# dev_kit.net
KiCad netlist of a schematic drawn in EasyEDA
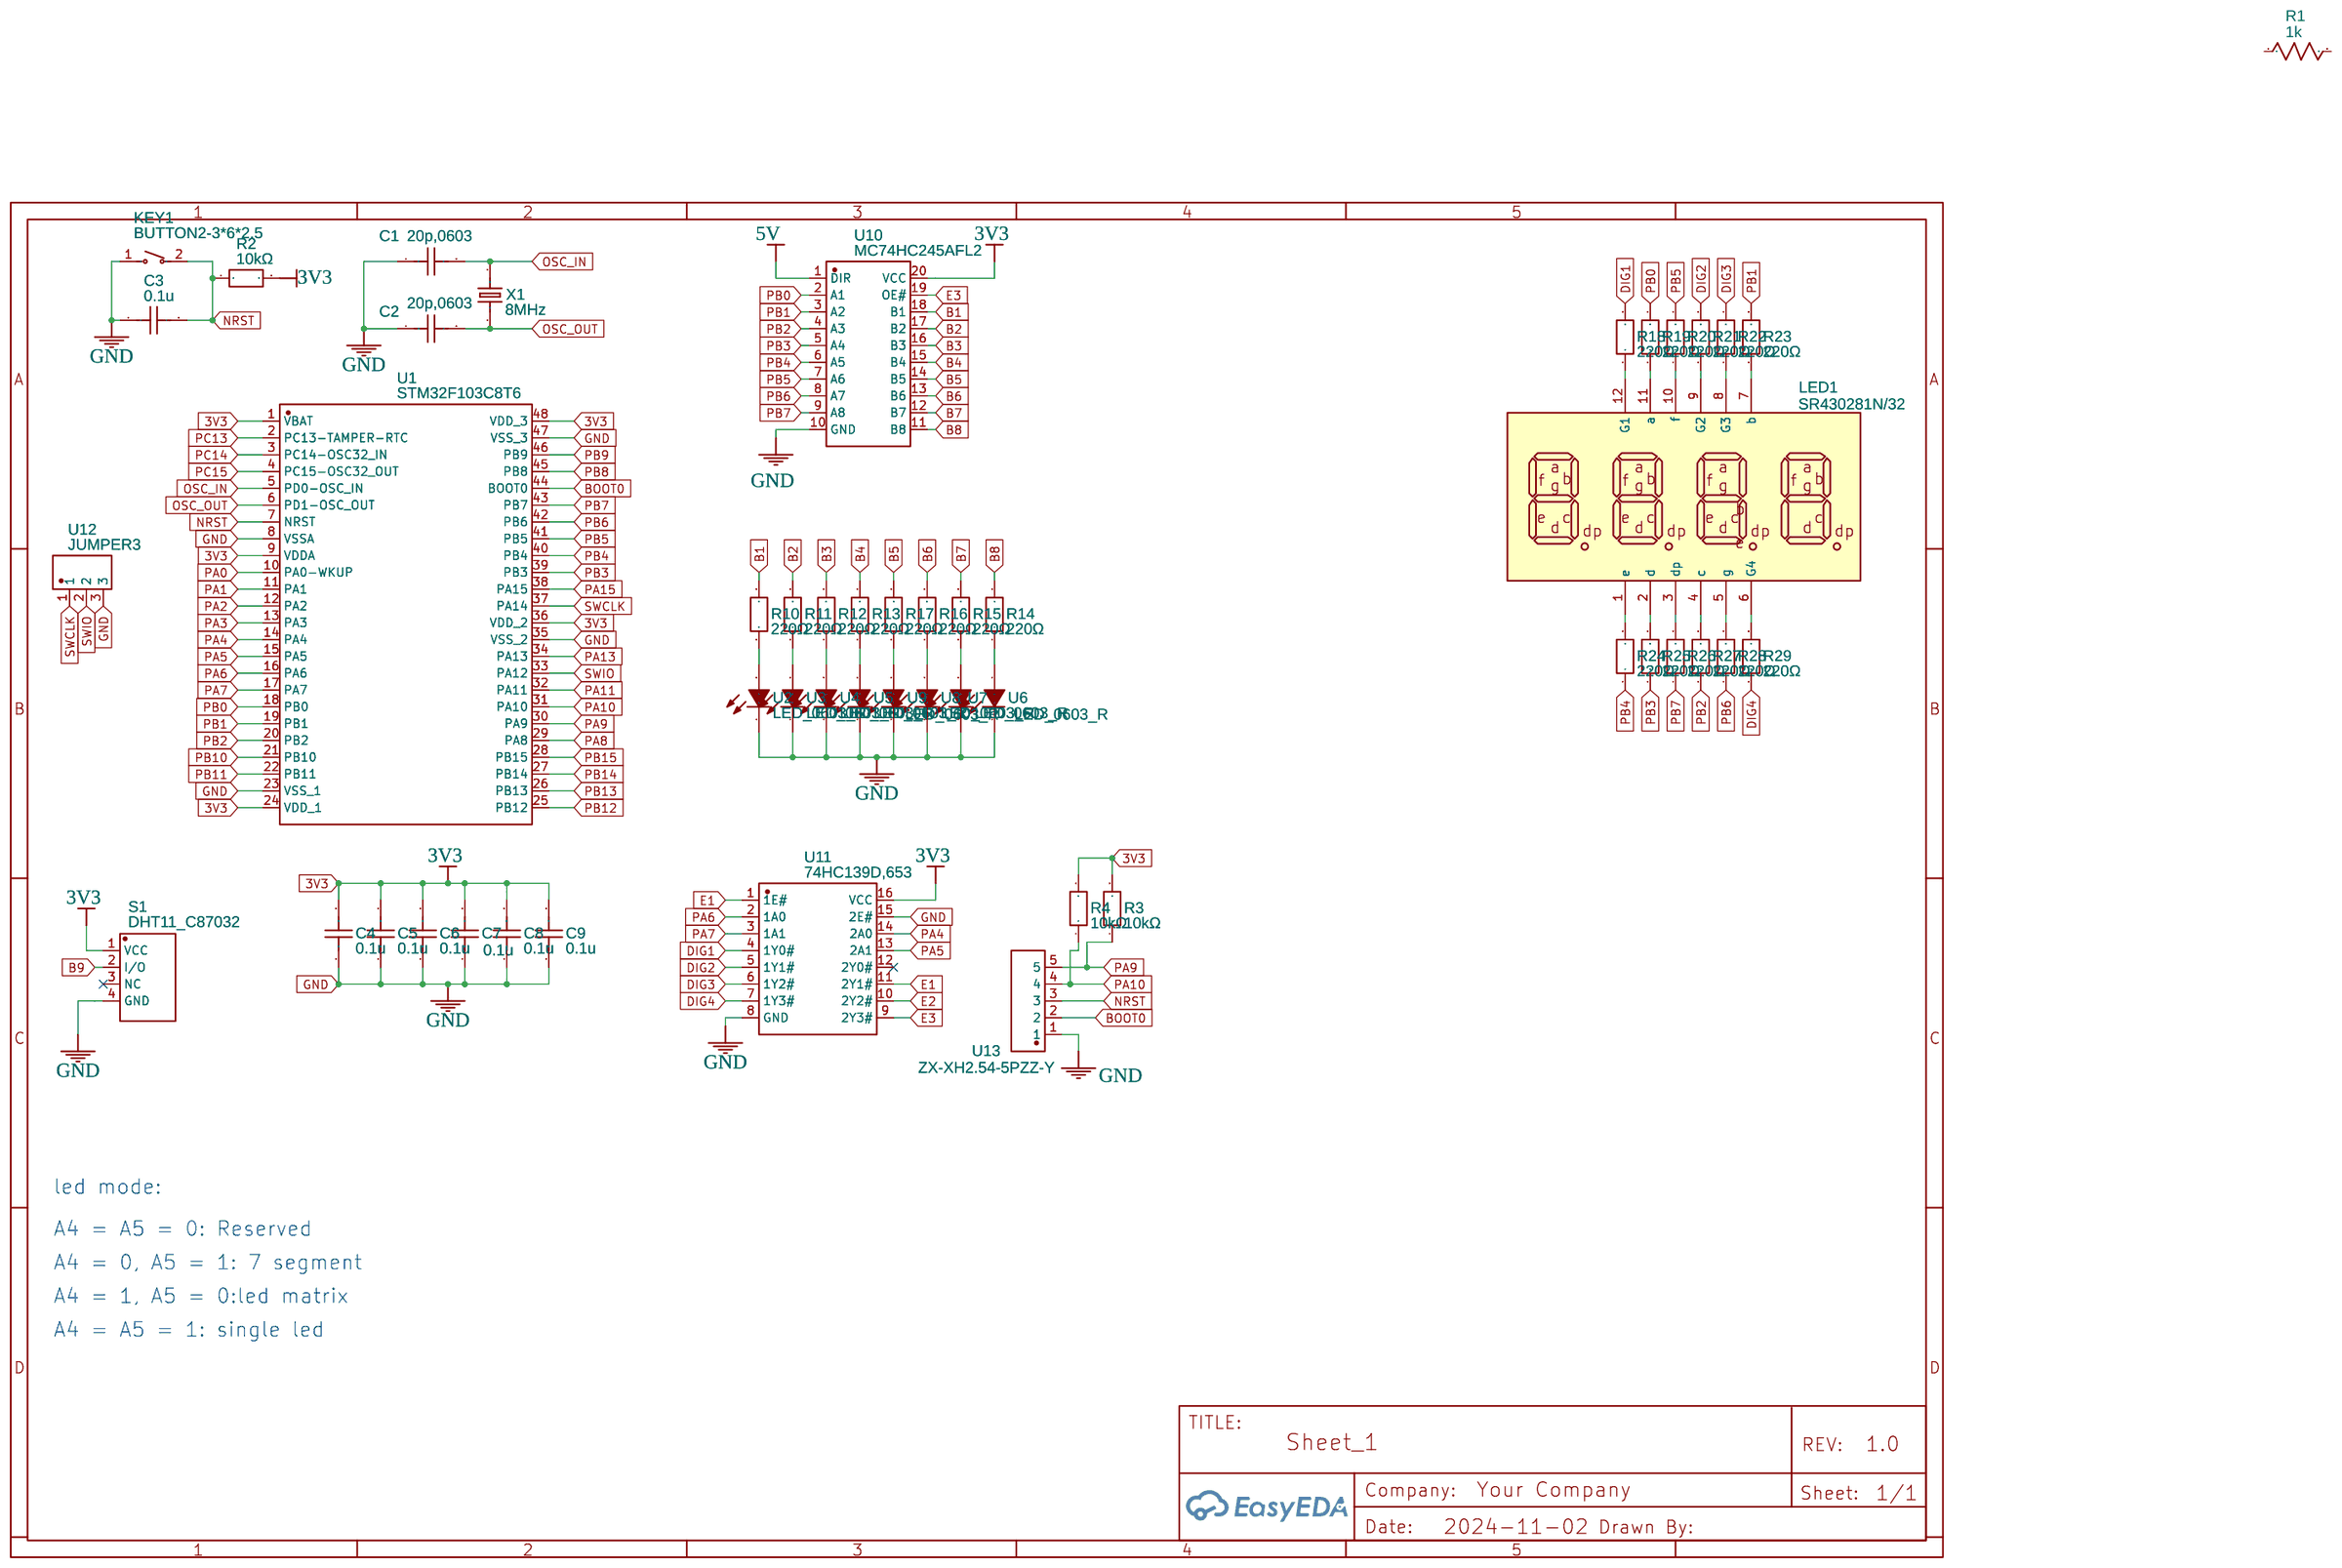
[diagram p0: schematic sheet]

(export (version "E")
  (design (tool "Eeschema 10.0.6"))
  (components
    (comp (ref "C1") (value "20p,0603") (libsource (lib "") (part "C_0603_US_1")))
    (comp (ref "C2") (value "20p,0603") (libsource (lib "") (part "C_0603_US_1")))
    (comp (ref "C3") (value "0.1u") (libsource (lib "") (part "C_0603_US_1")))
    (comp (ref "C4") (value "0.1u") (libsource (lib "") (part "C_0603_US")))
    (comp (ref "C5") (value "0.1u") (libsource (lib "") (part "C_0603_US")))
    (comp (ref "C6") (value "0.1u") (libsource (lib "") (part "C_0603_US")))
    (comp (ref "C7") (value "0.1u") (libsource (lib "") (part "C_0603_US")))
    (comp (ref "C8") (value "0.1u") (libsource (lib "") (part "C_0603_US")))
    (comp (ref "C9") (value "0.1u") (libsource (lib "") (part "C_0603_US")))
    (comp (ref "KEY1") (value "BUTTON2-3*6*2.5") (libsource (lib "") (part "BUTTON2-3*6*2.5")))
    (comp (ref "LED1")
      (value "SR430281N/32")
      (fields (field (name "Manufacturer") "ARKLED(方舟)"))
      (libsource (lib "") (part "SR430281N/32"))
    )
    (comp (ref "R1") (value "1k") (libsource (lib "") (part "R_0603_US")))
    (comp (ref "R2")
      (value "10kΩ")
      (fields (field (name "Manufacturer Part") "TD03E1002BT") (field (name "Manufacturer") "FH(风华)"))
      (libsource (lib "") (part "TD03E1002BT_1"))
    )
    (comp (ref "R3")
      (value "10kΩ")
      (fields (field (name "Manufacturer Part") "TD03E1002BT") (field (name "Manufacturer") "FH(风华)"))
      (libsource (lib "") (part "TD03E1002BT"))
    )
    (comp (ref "R4")
      (value "10kΩ")
      (fields (field (name "Manufacturer Part") "TD03E1002BT") (field (name "Manufacturer") "FH(风华)"))
      (libsource (lib "") (part "TD03E1002BT"))
    )
    (comp (ref "R10")
      (value "220Ω")
      (fields
        (field (name "Manufacturer Part") "CRCW0603220RFKEA")
        (field (name "Manufacturer") "VISHAY(威世)")
      )
      (libsource (lib "") (part "CRCW0603220RFKEA"))
    )
    (comp (ref "R11")
      (value "220Ω")
      (fields
        (field (name "Manufacturer Part") "CRCW0603220RFKEA")
        (field (name "Manufacturer") "VISHAY(威世)")
      )
      (libsource (lib "") (part "CRCW0603220RFKEA"))
    )
    (comp (ref "R12")
      (value "220Ω")
      (fields
        (field (name "Manufacturer Part") "CRCW0603220RFKEA")
        (field (name "Manufacturer") "VISHAY(威世)")
      )
      (libsource (lib "") (part "CRCW0603220RFKEA"))
    )
    (comp (ref "R13")
      (value "220Ω")
      (fields
        (field (name "Manufacturer Part") "CRCW0603220RFKEA")
        (field (name "Manufacturer") "VISHAY(威世)")
      )
      (libsource (lib "") (part "CRCW0603220RFKEA"))
    )
    (comp (ref "R14")
      (value "220Ω")
      (fields
        (field (name "Manufacturer Part") "CRCW0603220RFKEA")
        (field (name "Manufacturer") "VISHAY(威世)")
      )
      (libsource (lib "") (part "CRCW0603220RFKEA"))
    )
    (comp (ref "R15")
      (value "220Ω")
      (fields
        (field (name "Manufacturer Part") "CRCW0603220RFKEA")
        (field (name "Manufacturer") "VISHAY(威世)")
      )
      (libsource (lib "") (part "CRCW0603220RFKEA"))
    )
    (comp (ref "R16")
      (value "220Ω")
      (fields
        (field (name "Manufacturer Part") "CRCW0603220RFKEA")
        (field (name "Manufacturer") "VISHAY(威世)")
      )
      (libsource (lib "") (part "CRCW0603220RFKEA"))
    )
    (comp (ref "R17")
      (value "220Ω")
      (fields
        (field (name "Manufacturer Part") "CRCW0603220RFKEA")
        (field (name "Manufacturer") "VISHAY(威世)")
      )
      (libsource (lib "") (part "CRCW0603220RFKEA"))
    )
    (comp (ref "R18")
      (value "220Ω")
      (fields
        (field (name "Manufacturer Part") "CRCW0603220RFKEA")
        (field (name "Manufacturer") "VISHAY(威世)")
      )
      (libsource (lib "") (part "CRCW0603220RFKEA"))
    )
    (comp (ref "R19")
      (value "220Ω")
      (fields
        (field (name "Manufacturer Part") "CRCW0603220RFKEA")
        (field (name "Manufacturer") "VISHAY(威世)")
      )
      (libsource (lib "") (part "CRCW0603220RFKEA"))
    )
    (comp (ref "R20")
      (value "220Ω")
      (fields
        (field (name "Manufacturer Part") "CRCW0603220RFKEA")
        (field (name "Manufacturer") "VISHAY(威世)")
      )
      (libsource (lib "") (part "CRCW0603220RFKEA"))
    )
    (comp (ref "R21")
      (value "220Ω")
      (fields
        (field (name "Manufacturer Part") "CRCW0603220RFKEA")
        (field (name "Manufacturer") "VISHAY(威世)")
      )
      (libsource (lib "") (part "CRCW0603220RFKEA"))
    )
    (comp (ref "R22")
      (value "220Ω")
      (fields
        (field (name "Manufacturer Part") "CRCW0603220RFKEA")
        (field (name "Manufacturer") "VISHAY(威世)")
      )
      (libsource (lib "") (part "CRCW0603220RFKEA"))
    )
    (comp (ref "R23")
      (value "220Ω")
      (fields
        (field (name "Manufacturer Part") "CRCW0603220RFKEA")
        (field (name "Manufacturer") "VISHAY(威世)")
      )
      (libsource (lib "") (part "CRCW0603220RFKEA"))
    )
    (comp (ref "R24")
      (value "220Ω")
      (fields
        (field (name "Manufacturer Part") "CRCW0603220RFKEA")
        (field (name "Manufacturer") "VISHAY(威世)")
      )
      (libsource (lib "") (part "CRCW0603220RFKEA"))
    )
    (comp (ref "R25")
      (value "220Ω")
      (fields
        (field (name "Manufacturer Part") "CRCW0603220RFKEA")
        (field (name "Manufacturer") "VISHAY(威世)")
      )
      (libsource (lib "") (part "CRCW0603220RFKEA"))
    )
    (comp (ref "R26")
      (value "220Ω")
      (fields
        (field (name "Manufacturer Part") "CRCW0603220RFKEA")
        (field (name "Manufacturer") "VISHAY(威世)")
      )
      (libsource (lib "") (part "CRCW0603220RFKEA"))
    )
    (comp (ref "R27")
      (value "220Ω")
      (fields
        (field (name "Manufacturer Part") "CRCW0603220RFKEA")
        (field (name "Manufacturer") "VISHAY(威世)")
      )
      (libsource (lib "") (part "CRCW0603220RFKEA"))
    )
    (comp (ref "R28")
      (value "220Ω")
      (fields
        (field (name "Manufacturer Part") "CRCW0603220RFKEA")
        (field (name "Manufacturer") "VISHAY(威世)")
      )
      (libsource (lib "") (part "CRCW0603220RFKEA"))
    )
    (comp (ref "R29")
      (value "220Ω")
      (fields
        (field (name "Manufacturer Part") "CRCW0603220RFKEA")
        (field (name "Manufacturer") "VISHAY(威世)")
      )
      (libsource (lib "") (part "CRCW0603220RFKEA"))
    )
    (comp (ref "S1")
      (value "DHT11_C87032")
      (fields (field (name "Manufacturer Part") "DHT11") (field (name "Manufacturer") "AOSONG"))
      (libsource (lib "") (part "DHT11_C87032"))
    )
    (comp (ref "U1")
      (value "STM32F103C8T6")
      (fields (field (name "Manufacturer") "ST(意法半导体)"))
      (libsource (lib "") (part "STM32F103C8T6"))
    )
    (comp (ref "U2") (value "LED_0603_R") (libsource (lib "") (part "LED_0603_R")))
    (comp (ref "U3") (value "LED_0603_R") (libsource (lib "") (part "LED_0603_R")))
    (comp (ref "U4") (value "LED_0603_R") (libsource (lib "") (part "LED_0603_R")))
    (comp (ref "U5") (value "LED_0603_R") (libsource (lib "") (part "LED_0603_R")))
    (comp (ref "U6") (value "LED_0603_R") (libsource (lib "") (part "LED_0603_R")))
    (comp (ref "U7") (value "LED_0603_R") (libsource (lib "") (part "LED_0603_R")))
    (comp (ref "U8") (value "LED_0603_R") (libsource (lib "") (part "LED_0603_R")))
    (comp (ref "U9") (value "LED_0603_R") (libsource (lib "") (part "LED_0603_R")))
    (comp (ref "U10")
      (value "MC74HC245AFL2")
      (fields (field (name "Manufacturer") "MOTOROLA(摩托罗拉)"))
      (libsource (lib "") (part "MC74HC245AFL2"))
    )
    (comp (ref "U11")
      (value "74HC139D,653")
      (fields (field (name "Manufacturer") "Nexperia(安世)"))
      (libsource (lib "") (part "74HC139D,653"))
    )
    (comp (ref "U12")
      (value "JUMPER3")
      (fields (field (name "Manufacturer Part") "Jumper3"))
      (libsource (lib "") (part "JUMPER3"))
    )
    (comp (ref "U13")
      (value "ZX-XH2.54-5PZZ-Y")
      (fields (field (name "Manufacturer") "Megastar(兆星)"))
      (libsource (lib "") (part "ZX-XH2.54-5PZZ-Y"))
    )
    (comp (ref "X1")
      (value "8MHz")
      (fields
        (field (name "Manufacturer Part") "49S-8.00-20-10-10/A")
        (field (name "Manufacturer") "LIMING(利明)")
      )
      (libsource (lib "") (part "49S-8.00-20-10-10/A"))
    )
  )
  (nets
    (net (code "1") (name "3V3") (class "Default")
      (node (ref "C4") (pin "2") (pinfunction "2_2") (pintype "unspecified"))
      (node (ref "C5") (pin "2") (pinfunction "2_2") (pintype "unspecified"))
      (node (ref "C6") (pin "2") (pinfunction "2_2") (pintype "unspecified"))
      (node (ref "C7") (pin "2") (pinfunction "2_2") (pintype "unspecified"))
      (node (ref "C8") (pin "2") (pinfunction "2_2") (pintype "unspecified"))
      (node (ref "C9") (pin "2") (pinfunction "2_2") (pintype "unspecified"))
      (node (ref "R2") (pin "2") (pinfunction "2_2") (pintype "unspecified"))
      (node (ref "R3") (pin "2") (pinfunction "2_2") (pintype "unspecified"))
      (node (ref "R4") (pin "2") (pinfunction "2_2") (pintype "unspecified"))
      (node (ref "S1") (pin "1") (pinfunction "VCC_1") (pintype "unspecified"))
      (node (ref "U1") (pin "1") (pinfunction "VBAT_1") (pintype "unspecified"))
      (node (ref "U1") (pin "24") (pinfunction "VDD_1_24") (pintype "unspecified"))
      (node (ref "U1") (pin "36") (pinfunction "VDD_2_36") (pintype "unspecified"))
      (node (ref "U1") (pin "48") (pinfunction "VDD_3_48") (pintype "unspecified"))
      (node (ref "U1") (pin "9") (pinfunction "VDDA_9") (pintype "unspecified"))
      (node (ref "U10") (pin "20") (pinfunction "VCC_20") (pintype "unspecified"))
      (node (ref "U11") (pin "16") (pinfunction "VCC_16") (pintype "unspecified"))
    )
    (net (code "2") (name "5V") (class "Default")
      (node (ref "U10") (pin "1") (pinfunction "DIR_1") (pintype "unspecified"))
    )
    (net (code "3") (name "B1") (class "Default")
      (node (ref "R10") (pin "2") (pinfunction "2_2") (pintype "unspecified"))
      (node (ref "U10") (pin "18") (pinfunction "B1_18") (pintype "unspecified"))
    )
    (net (code "4") (name "B2") (class "Default")
      (node (ref "R11") (pin "2") (pinfunction "2_2") (pintype "unspecified"))
      (node (ref "U10") (pin "17") (pinfunction "B2_17") (pintype "unspecified"))
    )
    (net (code "5") (name "B3") (class "Default")
      (node (ref "R12") (pin "2") (pinfunction "2_2") (pintype "unspecified"))
      (node (ref "U10") (pin "16") (pinfunction "B3_16") (pintype "unspecified"))
    )
    (net (code "6") (name "B4") (class "Default")
      (node (ref "R13") (pin "2") (pinfunction "2_2") (pintype "unspecified"))
      (node (ref "U10") (pin "15") (pinfunction "B4_15") (pintype "unspecified"))
    )
    (net (code "7") (name "B5") (class "Default")
      (node (ref "R17") (pin "2") (pinfunction "2_2") (pintype "unspecified"))
      (node (ref "U10") (pin "14") (pinfunction "B5_14") (pintype "unspecified"))
    )
    (net (code "8") (name "B6") (class "Default")
      (node (ref "R16") (pin "2") (pinfunction "2_2") (pintype "unspecified"))
      (node (ref "U10") (pin "13") (pinfunction "B6_13") (pintype "unspecified"))
    )
    (net (code "9") (name "B7") (class "Default")
      (node (ref "R15") (pin "2") (pinfunction "2_2") (pintype "unspecified"))
      (node (ref "U10") (pin "12") (pinfunction "B7_12") (pintype "unspecified"))
    )
    (net (code "10") (name "B8") (class "Default")
      (node (ref "R14") (pin "2") (pinfunction "2_2") (pintype "unspecified"))
      (node (ref "U10") (pin "11") (pinfunction "B8_11") (pintype "unspecified"))
    )
    (net (code "11") (name "B9") (class "Default")
      (node (ref "S1") (pin "2") (pinfunction "I/O_2") (pintype "unspecified"))
    )
    (net (code "12") (name "BOOT0") (class "Default")
      (node (ref "U1") (pin "44") (pinfunction "BOOT0_44") (pintype "unspecified"))
      (node (ref "U13") (pin "2") (pinfunction "2_2") (pintype "unspecified"))
    )
    (net (code "13") (name "DIG1") (class "Default")
      (node (ref "R18") (pin "2") (pinfunction "2_2") (pintype "unspecified"))
      (node (ref "U11") (pin "4") (pinfunction "1Y0#_4") (pintype "unspecified"))
    )
    (net (code "14") (name "DIG2") (class "Default")
      (node (ref "R21") (pin "2") (pinfunction "2_2") (pintype "unspecified"))
      (node (ref "U11") (pin "5") (pinfunction "1Y1#_5") (pintype "unspecified"))
    )
    (net (code "15") (name "DIG3") (class "Default")
      (node (ref "R22") (pin "2") (pinfunction "2_2") (pintype "unspecified"))
      (node (ref "U11") (pin "6") (pinfunction "1Y2#_6") (pintype "unspecified"))
    )
    (net (code "16") (name "DIG4") (class "Default")
      (node (ref "R29") (pin "1") (pinfunction "1_1") (pintype "unspecified"))
      (node (ref "U11") (pin "7") (pinfunction "1Y3#_7") (pintype "unspecified"))
    )
    (net (code "17") (name "E1") (class "Default")
      (node (ref "U11") (pin "1") (pinfunction "1E#_1") (pintype "unspecified"))
      (node (ref "U11") (pin "11") (pinfunction "2Y1#_11") (pintype "unspecified"))
    )
    (net (code "18") (name "E2") (class "Default")
      (node (ref "U11") (pin "10") (pinfunction "2Y2#_10") (pintype "unspecified"))
    )
    (net (code "19") (name "E3") (class "Default")
      (node (ref "U10") (pin "19") (pinfunction "OE#_19") (pintype "unspecified"))
      (node (ref "U11") (pin "9") (pinfunction "2Y3#_9") (pintype "unspecified"))
    )
    (net (code "20") (name "GND") (class "Default")
      (node (ref "C1") (pin "1") (pinfunction "1_1") (pintype "unspecified"))
      (node (ref "C2") (pin "1") (pinfunction "1_1") (pintype "unspecified"))
      (node (ref "C3") (pin "1") (pinfunction "1_1") (pintype "unspecified"))
      (node (ref "C4") (pin "1") (pinfunction "1_1") (pintype "unspecified"))
      (node (ref "C5") (pin "1") (pinfunction "1_1") (pintype "unspecified"))
      (node (ref "C6") (pin "1") (pinfunction "1_1") (pintype "unspecified"))
      (node (ref "C7") (pin "1") (pinfunction "1_1") (pintype "unspecified"))
      (node (ref "C8") (pin "1") (pinfunction "1_1") (pintype "unspecified"))
      (node (ref "C9") (pin "1") (pinfunction "1_1") (pintype "unspecified"))
      (node (ref "KEY1") (pin "1") (pinfunction "1_1") (pintype "unspecified"))
      (node (ref "S1") (pin "4") (pinfunction "GND_4") (pintype "unspecified"))
      (node (ref "U1") (pin "23") (pinfunction "VSS_1_23") (pintype "unspecified"))
      (node (ref "U1") (pin "35") (pinfunction "VSS_2_35") (pintype "unspecified"))
      (node (ref "U1") (pin "47") (pinfunction "VSS_3_47") (pintype "unspecified"))
      (node (ref "U1") (pin "8") (pinfunction "VSSA_8") (pintype "unspecified"))
      (node (ref "U10") (pin "10") (pinfunction "GND_10") (pintype "unspecified"))
      (node (ref "U11") (pin "15") (pinfunction "2E#_15") (pintype "unspecified"))
      (node (ref "U11") (pin "8") (pinfunction "GND_8") (pintype "unspecified"))
      (node (ref "U12") (pin "3") (pinfunction "3_3") (pintype "unspecified"))
      (node (ref "U13") (pin "1") (pinfunction "1_1") (pintype "unspecified"))
      (node (ref "U2") (pin "1") (pinfunction "-_1") (pintype "input"))
      (node (ref "U3") (pin "1") (pinfunction "-_1") (pintype "input"))
      (node (ref "U4") (pin "1") (pinfunction "-_1") (pintype "input"))
      (node (ref "U5") (pin "1") (pinfunction "-_1") (pintype "input"))
      (node (ref "U6") (pin "1") (pinfunction "-_1") (pintype "input"))
      (node (ref "U7") (pin "1") (pinfunction "-_1") (pintype "input"))
      (node (ref "U8") (pin "1") (pinfunction "-_1") (pintype "input"))
      (node (ref "U9") (pin "1") (pinfunction "-_1") (pintype "input"))
    )
    (net (code "21") (name "NRST") (class "Default")
      (node (ref "C3") (pin "2") (pinfunction "2_2") (pintype "unspecified"))
      (node (ref "KEY1") (pin "2") (pinfunction "2_2") (pintype "unspecified"))
      (node (ref "R2") (pin "1") (pinfunction "1_1") (pintype "unspecified"))
      (node (ref "U1") (pin "7") (pinfunction "NRST_7") (pintype "unspecified"))
      (node (ref "U13") (pin "3") (pinfunction "3_3") (pintype "unspecified"))
    )
    (net (code "22") (name "Net-(LED1-G1)") (class "Default")
      (node (ref "LED1") (pin "12") (pinfunction "G1_12") (pintype "input"))
      (node (ref "R18") (pin "1") (pinfunction "1_1") (pintype "unspecified"))
    )
    (net (code "23") (name "Net-(LED1-G2)") (class "Default")
      (node (ref "LED1") (pin "9") (pinfunction "G2_9") (pintype "input"))
      (node (ref "R21") (pin "1") (pinfunction "1_1") (pintype "unspecified"))
    )
    (net (code "24") (name "Net-(LED1-G3)") (class "Default")
      (node (ref "LED1") (pin "8") (pinfunction "G3_8") (pintype "input"))
      (node (ref "R22") (pin "1") (pinfunction "1_1") (pintype "unspecified"))
    )
    (net (code "25") (name "Net-(LED1-G4)") (class "Default")
      (node (ref "LED1") (pin "6") (pinfunction "G4_6") (pintype "input"))
      (node (ref "R29") (pin "2") (pinfunction "2_2") (pintype "unspecified"))
    )
    (net (code "26") (name "Net-(LED1-a)") (class "Default")
      (node (ref "LED1") (pin "11") (pinfunction "a_11") (pintype "input"))
      (node (ref "R19") (pin "1") (pinfunction "1_1") (pintype "unspecified"))
    )
    (net (code "27") (name "Net-(LED1-b)") (class "Default")
      (node (ref "LED1") (pin "7") (pinfunction "b_7") (pintype "input"))
      (node (ref "R23") (pin "1") (pinfunction "1_1") (pintype "unspecified"))
    )
    (net (code "28") (name "Net-(LED1-c)") (class "Default")
      (node (ref "LED1") (pin "4") (pinfunction "c_4") (pintype "input"))
      (node (ref "R27") (pin "2") (pinfunction "2_2") (pintype "unspecified"))
    )
    (net (code "29") (name "Net-(LED1-d)") (class "Default")
      (node (ref "LED1") (pin "2") (pinfunction "d_2") (pintype "input"))
      (node (ref "R25") (pin "2") (pinfunction "2_2") (pintype "unspecified"))
    )
    (net (code "30") (name "Net-(LED1-dp)") (class "Default")
      (node (ref "LED1") (pin "3") (pinfunction "dp_3") (pintype "input"))
      (node (ref "R26") (pin "2") (pinfunction "2_2") (pintype "unspecified"))
    )
    (net (code "31") (name "Net-(LED1-e)") (class "Default")
      (node (ref "LED1") (pin "1") (pinfunction "e_1") (pintype "input"))
      (node (ref "R24") (pin "2") (pinfunction "2_2") (pintype "unspecified"))
    )
    (net (code "32") (name "Net-(LED1-f)") (class "Default")
      (node (ref "LED1") (pin "10") (pinfunction "f_10") (pintype "input"))
      (node (ref "R20") (pin "1") (pinfunction "1_1") (pintype "unspecified"))
    )
    (net (code "33") (name "Net-(LED1-g)") (class "Default")
      (node (ref "LED1") (pin "5") (pinfunction "g_5") (pintype "input"))
      (node (ref "R28") (pin "2") (pinfunction "2_2") (pintype "unspecified"))
    )
    (net (code "34") (name "Net-(U2-+)") (class "Default")
      (node (ref "R10") (pin "1") (pinfunction "1_1") (pintype "unspecified"))
      (node (ref "U2") (pin "2") (pinfunction "+_2") (pintype "input"))
    )
    (net (code "35") (name "Net-(U3-+)") (class "Default")
      (node (ref "R11") (pin "1") (pinfunction "1_1") (pintype "unspecified"))
      (node (ref "U3") (pin "2") (pinfunction "+_2") (pintype "input"))
    )
    (net (code "36") (name "Net-(U4-+)") (class "Default")
      (node (ref "R12") (pin "1") (pinfunction "1_1") (pintype "unspecified"))
      (node (ref "U4") (pin "2") (pinfunction "+_2") (pintype "input"))
    )
    (net (code "37") (name "Net-(U5-+)") (class "Default")
      (node (ref "R13") (pin "1") (pinfunction "1_1") (pintype "unspecified"))
      (node (ref "U5") (pin "2") (pinfunction "+_2") (pintype "input"))
    )
    (net (code "38") (name "Net-(U6-+)") (class "Default")
      (node (ref "R14") (pin "1") (pinfunction "1_1") (pintype "unspecified"))
      (node (ref "U6") (pin "2") (pinfunction "+_2") (pintype "input"))
    )
    (net (code "39") (name "Net-(U7-+)") (class "Default")
      (node (ref "R15") (pin "1") (pinfunction "1_1") (pintype "unspecified"))
      (node (ref "U7") (pin "2") (pinfunction "+_2") (pintype "input"))
    )
    (net (code "40") (name "Net-(U8-+)") (class "Default")
      (node (ref "R16") (pin "1") (pinfunction "1_1") (pintype "unspecified"))
      (node (ref "U8") (pin "2") (pinfunction "+_2") (pintype "input"))
    )
    (net (code "41") (name "Net-(U9-+)") (class "Default")
      (node (ref "R17") (pin "1") (pinfunction "1_1") (pintype "unspecified"))
      (node (ref "U9") (pin "2") (pinfunction "+_2") (pintype "input"))
    )
    (net (code "42") (name "OSC_IN") (class "Default")
      (node (ref "C1") (pin "2") (pinfunction "2_2") (pintype "unspecified"))
      (node (ref "U1") (pin "5") (pinfunction "PD0-OSC_IN_5") (pintype "unspecified"))
      (node (ref "X1") (pin "2") (pinfunction "2_2") (pintype "unspecified"))
    )
    (net (code "43") (name "OSC_OUT") (class "Default")
      (node (ref "C2") (pin "2") (pinfunction "2_2") (pintype "unspecified"))
      (node (ref "U1") (pin "6") (pinfunction "PD1-OSC_OUT_6") (pintype "unspecified"))
      (node (ref "X1") (pin "1") (pinfunction "1_1") (pintype "unspecified"))
    )
    (net (code "44") (name "PA0") (class "Default")
      (node (ref "U1") (pin "10") (pinfunction "PA0-WKUP_10") (pintype "unspecified"))
    )
    (net (code "45") (name "PA1") (class "Default")
      (node (ref "U1") (pin "11") (pinfunction "PA1_11") (pintype "unspecified"))
    )
    (net (code "46") (name "PA2") (class "Default")
      (node (ref "U1") (pin "12") (pinfunction "PA2_12") (pintype "unspecified"))
    )
    (net (code "47") (name "PA3") (class "Default")
      (node (ref "U1") (pin "13") (pinfunction "PA3_13") (pintype "unspecified"))
    )
    (net (code "48") (name "PA4") (class "Default")
      (node (ref "U1") (pin "14") (pinfunction "PA4_14") (pintype "unspecified"))
      (node (ref "U11") (pin "14") (pinfunction "2A0_14") (pintype "unspecified"))
    )
    (net (code "49") (name "PA5") (class "Default")
      (node (ref "U1") (pin "15") (pinfunction "PA5_15") (pintype "unspecified"))
      (node (ref "U11") (pin "13") (pinfunction "2A1_13") (pintype "unspecified"))
    )
    (net (code "50") (name "PA6") (class "Default")
      (node (ref "U1") (pin "16") (pinfunction "PA6_16") (pintype "unspecified"))
      (node (ref "U11") (pin "2") (pinfunction "1A0_2") (pintype "unspecified"))
    )
    (net (code "51") (name "PA7") (class "Default")
      (node (ref "U1") (pin "17") (pinfunction "PA7_17") (pintype "unspecified"))
      (node (ref "U11") (pin "3") (pinfunction "1A1_3") (pintype "unspecified"))
    )
    (net (code "52") (name "PA8") (class "Default")
      (node (ref "U1") (pin "29") (pinfunction "PA8_29") (pintype "unspecified"))
    )
    (net (code "53") (name "PA9") (class "Default")
      (node (ref "R3") (pin "1") (pinfunction "1_1") (pintype "unspecified"))
      (node (ref "U1") (pin "30") (pinfunction "PA9_30") (pintype "unspecified"))
      (node (ref "U13") (pin "5") (pinfunction "5_5") (pintype "unspecified"))
    )
    (net (code "54") (name "PA10") (class "Default")
      (node (ref "R4") (pin "1") (pinfunction "1_1") (pintype "unspecified"))
      (node (ref "U1") (pin "31") (pinfunction "PA10_31") (pintype "unspecified"))
      (node (ref "U13") (pin "4") (pinfunction "4_4") (pintype "unspecified"))
    )
    (net (code "55") (name "PA11") (class "Default")
      (node (ref "U1") (pin "32") (pinfunction "PA11_32") (pintype "unspecified"))
    )
    (net (code "56") (name "PA13") (class "Default")
      (node (ref "U1") (pin "34") (pinfunction "PA13_34") (pintype "unspecified"))
    )
    (net (code "57") (name "PA15") (class "Default")
      (node (ref "U1") (pin "38") (pinfunction "PA15_38") (pintype "unspecified"))
    )
    (net (code "58") (name "PB0") (class "Default")
      (node (ref "R19") (pin "2") (pinfunction "2_2") (pintype "unspecified"))
      (node (ref "U1") (pin "18") (pinfunction "PB0_18") (pintype "unspecified"))
      (node (ref "U10") (pin "2") (pinfunction "A1_2") (pintype "unspecified"))
    )
    (net (code "59") (name "PB1") (class "Default")
      (node (ref "R23") (pin "2") (pinfunction "2_2") (pintype "unspecified"))
      (node (ref "U1") (pin "19") (pinfunction "PB1_19") (pintype "unspecified"))
      (node (ref "U10") (pin "3") (pinfunction "A2_3") (pintype "unspecified"))
    )
    (net (code "60") (name "PB2") (class "Default")
      (node (ref "R27") (pin "1") (pinfunction "1_1") (pintype "unspecified"))
      (node (ref "U1") (pin "20") (pinfunction "PB2_20") (pintype "unspecified"))
      (node (ref "U10") (pin "4") (pinfunction "A3_4") (pintype "unspecified"))
    )
    (net (code "61") (name "PB3") (class "Default")
      (node (ref "R25") (pin "1") (pinfunction "1_1") (pintype "unspecified"))
      (node (ref "U1") (pin "39") (pinfunction "PB3_39") (pintype "unspecified"))
      (node (ref "U10") (pin "5") (pinfunction "A4_5") (pintype "unspecified"))
    )
    (net (code "62") (name "PB4") (class "Default")
      (node (ref "R24") (pin "1") (pinfunction "1_1") (pintype "unspecified"))
      (node (ref "U1") (pin "40") (pinfunction "PB4_40") (pintype "unspecified"))
      (node (ref "U10") (pin "6") (pinfunction "A5_6") (pintype "unspecified"))
    )
    (net (code "63") (name "PB5") (class "Default")
      (node (ref "R20") (pin "2") (pinfunction "2_2") (pintype "unspecified"))
      (node (ref "U1") (pin "41") (pinfunction "PB5_41") (pintype "unspecified"))
      (node (ref "U10") (pin "7") (pinfunction "A6_7") (pintype "unspecified"))
    )
    (net (code "64") (name "PB6") (class "Default")
      (node (ref "R28") (pin "1") (pinfunction "1_1") (pintype "unspecified"))
      (node (ref "U1") (pin "42") (pinfunction "PB6_42") (pintype "unspecified"))
      (node (ref "U10") (pin "8") (pinfunction "A7_8") (pintype "unspecified"))
    )
    (net (code "65") (name "PB7") (class "Default")
      (node (ref "R26") (pin "1") (pinfunction "1_1") (pintype "unspecified"))
      (node (ref "U1") (pin "43") (pinfunction "PB7_43") (pintype "unspecified"))
      (node (ref "U10") (pin "9") (pinfunction "A8_9") (pintype "unspecified"))
    )
    (net (code "66") (name "PB8") (class "Default")
      (node (ref "U1") (pin "45") (pinfunction "PB8_45") (pintype "unspecified"))
    )
    (net (code "67") (name "PB9") (class "Default")
      (node (ref "U1") (pin "46") (pinfunction "PB9_46") (pintype "unspecified"))
    )
    (net (code "68") (name "PB10") (class "Default")
      (node (ref "U1") (pin "21") (pinfunction "PB10_21") (pintype "unspecified"))
    )
    (net (code "69") (name "PB11") (class "Default")
      (node (ref "U1") (pin "22") (pinfunction "PB11_22") (pintype "unspecified"))
    )
    (net (code "70") (name "PB12") (class "Default")
      (node (ref "U1") (pin "25") (pinfunction "PB12_25") (pintype "unspecified"))
    )
    (net (code "71") (name "PB13") (class "Default")
      (node (ref "U1") (pin "26") (pinfunction "PB13_26") (pintype "unspecified"))
    )
    (net (code "72") (name "PB14") (class "Default")
      (node (ref "U1") (pin "27") (pinfunction "PB14_27") (pintype "unspecified"))
    )
    (net (code "73") (name "PB15") (class "Default")
      (node (ref "U1") (pin "28") (pinfunction "PB15_28") (pintype "unspecified"))
    )
    (net (code "74") (name "PC13") (class "Default")
      (node (ref "U1") (pin "2") (pinfunction "PC13-TAMPER-RTC_2") (pintype "unspecified"))
    )
    (net (code "75") (name "PC14") (class "Default")
      (node (ref "U1") (pin "3") (pinfunction "PC14-OSC32_IN_3") (pintype "unspecified"))
    )
    (net (code "76") (name "PC15") (class "Default")
      (node (ref "U1") (pin "4") (pinfunction "PC15-OSC32_OUT_4") (pintype "unspecified"))
    )
    (net (code "77") (name "SWCLK") (class "Default")
      (node (ref "U1") (pin "37") (pinfunction "PA14_37") (pintype "unspecified"))
      (node (ref "U12") (pin "1") (pinfunction "1_1") (pintype "unspecified"))
    )
    (net (code "78") (name "SWIO") (class "Default")
      (node (ref "U1") (pin "33") (pinfunction "PA12_33") (pintype "unspecified"))
      (node (ref "U12") (pin "2") (pinfunction "2_2") (pintype "unspecified"))
    )
    (net (code "79") (name "unconnected-(R1-Pad1)") (class "Default")
      (node (ref "R1") (pin "1") (pinfunction "1_1") (pintype "unspecified"))
    )
    (net (code "80") (name "unconnected-(R1-Pad2)") (class "Default")
      (node (ref "R1") (pin "2") (pinfunction "2_2") (pintype "unspecified"))
    )
    (net (code "81") (name "unconnected-(S1-NC-Pad3)") (class "Default")
      (node (ref "S1") (pin "3") (pinfunction "NC_3") (pintype "unspecified+no_connect"))
    )
    (net (code "82") (name "unconnected-(U11-2Y0#-Pad12)") (class "Default")
      (node (ref "U11") (pin "12") (pinfunction "2Y0#_12") (pintype "unspecified+no_connect"))
    )
  )
)
